# ncp1117.net
KiCad netlist of a schematic drawn in EAGLE
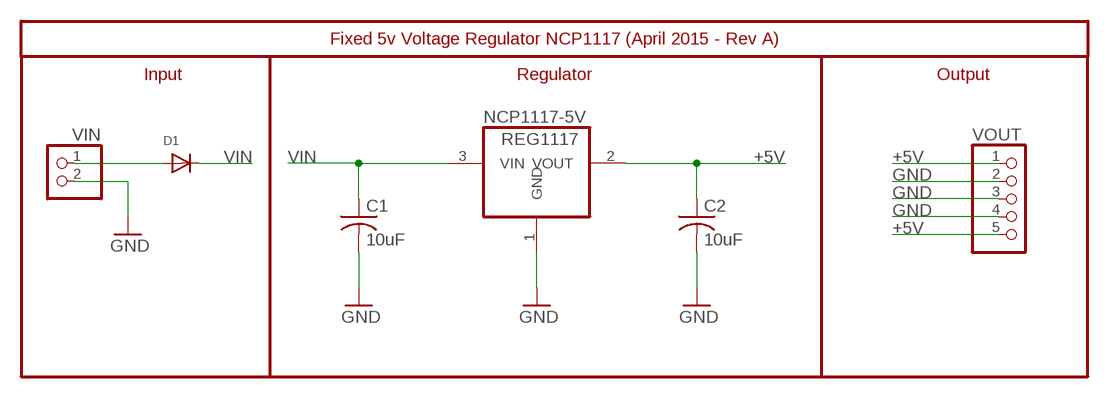
[diagram p0: schematic, sheet 1]

(export (version "E")
  (design (tool "Eeschema 10.0.6"))
  (components
    (comp (ref "C1")
      (value "10uF")
      (footprint "eagle-import:C0805")
      (libsource (lib "eagle-import") (part "C-USC0805"))
    )
    (comp (ref "C2")
      (value "10uF")
      (footprint "eagle-import:C0805")
      (libsource (lib "eagle-import") (part "C-USC0805"))
    )
    (comp (ref "D1")
      (value "DIODESMA")
      (footprint "eagle-import:SMADIODE")
      (libsource (lib "eagle-import") (part "DIODESMA"))
    )
    (comp (ref "NCP1117-5V")
      (value "REG1117")
      (footprint "eagle-import:SOT223")
      (libsource (lib "eagle-import") (part "REG1117"))
    )
    (comp (ref "VIN")
      (value "PINHD-1X2")
      (footprint "eagle-import:1X02")
      (libsource (lib "eagle-import") (part "PINHD-1X2"))
    )
    (comp (ref "VOUT")
      (value "PINHD-1X5")
      (footprint "eagle-import:1X05")
      (libsource (lib "eagle-import") (part "PINHD-1X5"))
    )
  )
  (nets
    (net (code "1") (name "/+5V") (class "Default")
      (node (ref "C2") (pin "1") (pinfunction "1_1") (pintype "passive"))
      (node (ref "NCP1117-5V") (pin "2") (pinfunction "VOUT_2") (pintype "output"))
      (node (ref "VOUT") (pin "1") (pinfunction "1_1") (pintype "passive"))
      (node (ref "VOUT") (pin "5") (pinfunction "5_5") (pintype "passive"))
    )
    (net (code "2") (name "/VIN") (class "Default")
      (node (ref "C1") (pin "1") (pinfunction "1_1") (pintype "passive"))
      (node (ref "D1") (pin "C") (pinfunction "C_C") (pintype "passive"))
      (node (ref "NCP1117-5V") (pin "3") (pinfunction "VIN_3") (pintype "input"))
    )
    (net (code "3") (name "GND") (class "Default")
      (node (ref "C1") (pin "2") (pinfunction "2_2") (pintype "passive"))
      (node (ref "C2") (pin "2") (pinfunction "2_2") (pintype "passive"))
      (node (ref "NCP1117-5V") (pin "1") (pinfunction "GND_1") (pintype "power_in"))
      (node (ref "VIN") (pin "2") (pinfunction "2_2") (pintype "passive"))
      (node (ref "VOUT") (pin "2") (pinfunction "2_2") (pintype "passive"))
      (node (ref "VOUT") (pin "3") (pinfunction "3_3") (pintype "passive"))
      (node (ref "VOUT") (pin "4") (pinfunction "4_4") (pintype "passive"))
    )
    (net (code "4") (name "Net-(D1-PadA)") (class "Default")
      (node (ref "D1") (pin "A") (pinfunction "A_A") (pintype "passive"))
      (node (ref "VIN") (pin "1") (pinfunction "1_1") (pintype "passive"))
    )
  )
)
